# MPL115A1-Breakout-v12.net
KiCad netlist of a schematic drawn in EAGLE
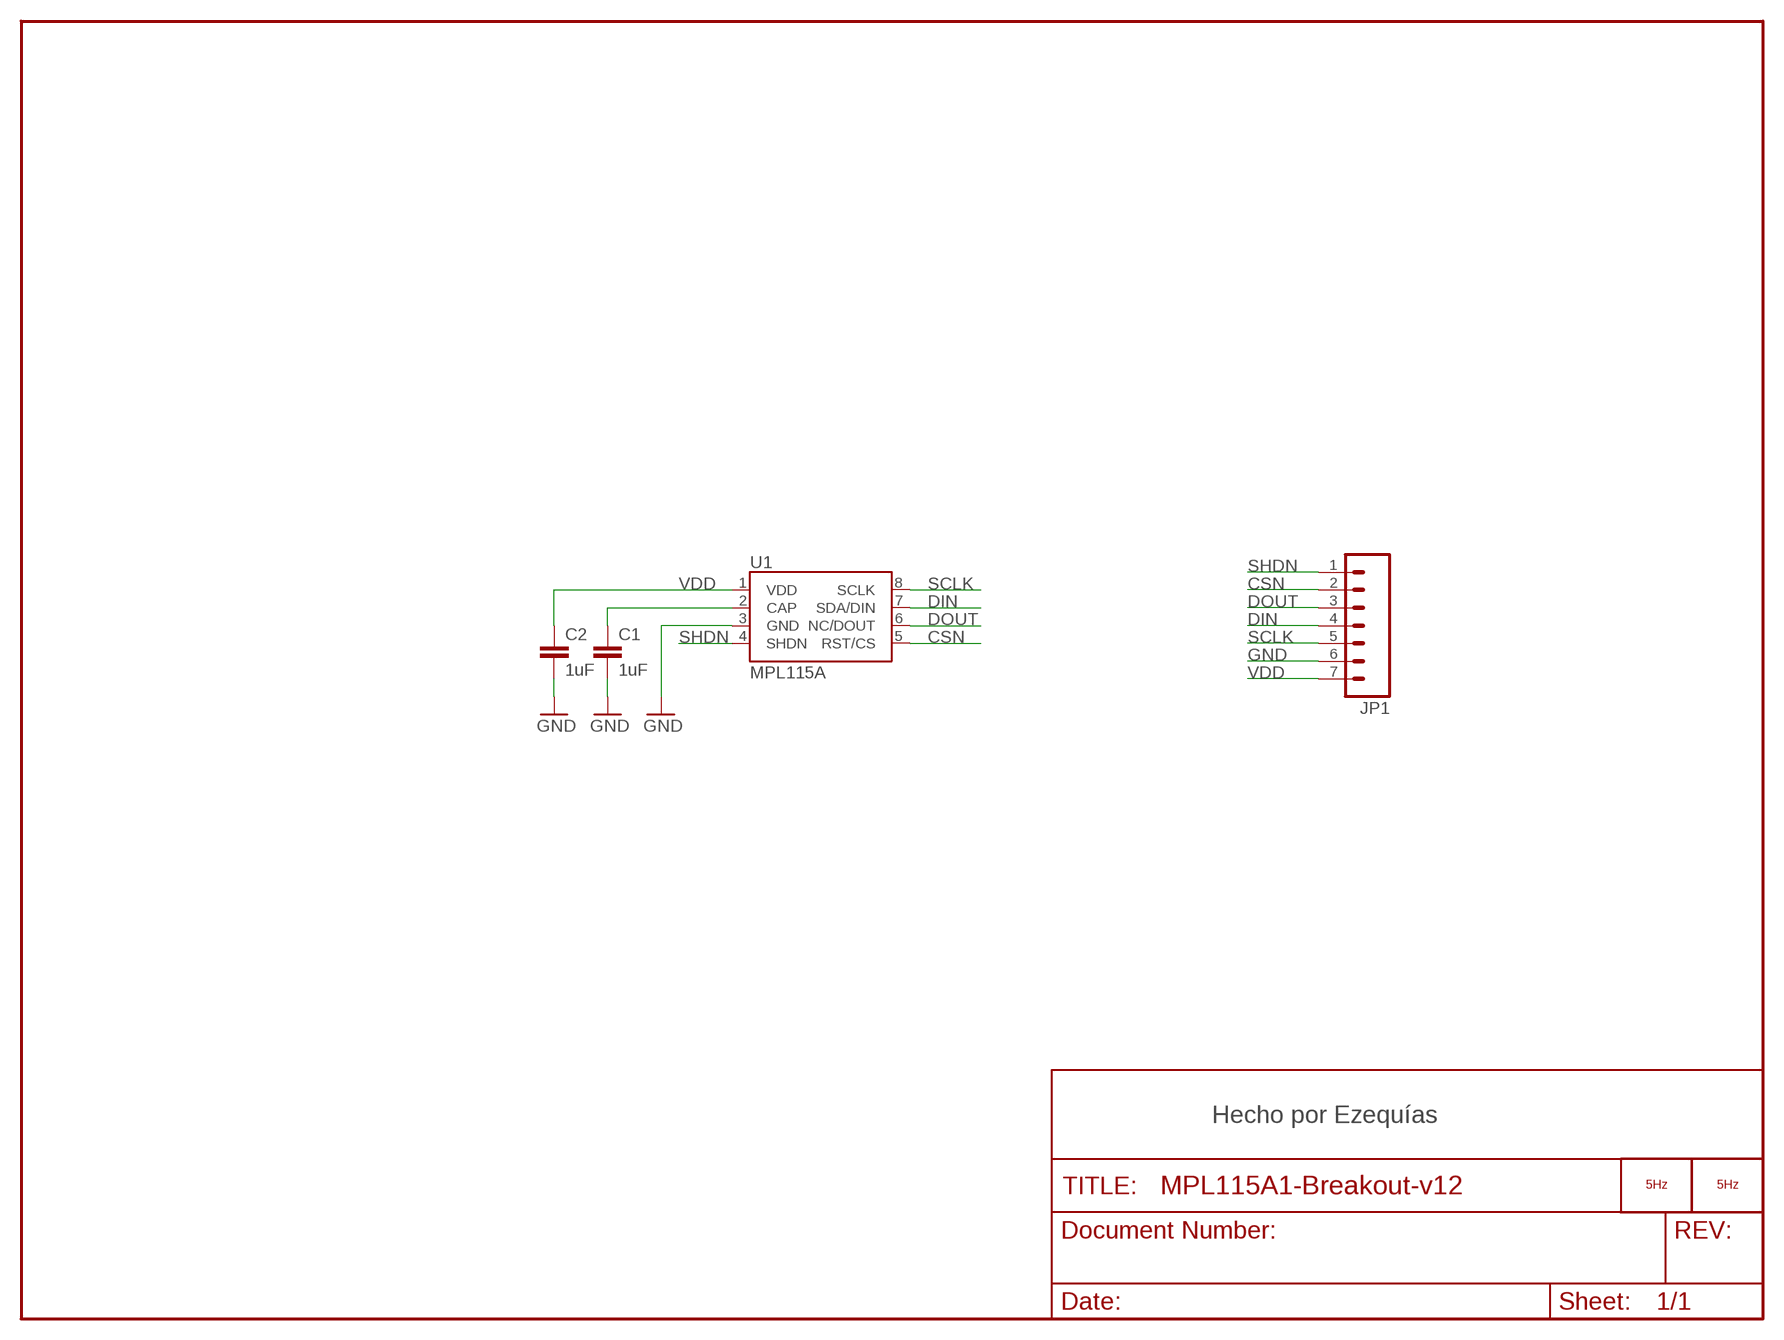
[diagram p0: schematic, sheet 1]

(export (version "E")
  (design (tool "Eeschema 10.0.6"))
  (components
    (comp (ref "C1")
      (value "1uF")
      (footprint "eagle-import:0603-CAP")
      (libsource (lib "eagle-import") (part "CAP0603-CAP"))
    )
    (comp (ref "C2")
      (value "1uF")
      (footprint "eagle-import:0603-CAP")
      (libsource (lib "eagle-import") (part "CAP0603-CAP"))
    )
    (comp (ref "JP1")
      (value "M07")
      (footprint "eagle-import:1X07")
      (libsource (lib "eagle-import") (part "M07"))
    )
    (comp (ref "LOGO1")
      (value "LOGO_5HZ_H_COOPER_10MM")
      (footprint "eagle-import:5HZ_LOGO_H_COOPER_10MM")
      (libsource (lib "eagle-import") (part "LOGO_5HZ_H_COOPER_10MM"))
    )
    (comp (ref "LOGO2")
      (value "LOGO_5HZ_H_5MM")
      (footprint "eagle-import:5HZ_LOGO_H_5MM")
      (libsource (lib "eagle-import") (part "LOGO_5HZ_H_5MM"))
    )
    (comp (ref "U1")
      (value "MPL115A")
      (footprint "eagle-import:LGA8")
      (libsource (lib "eagle-import") (part "MPL115A"))
    )
  )
  (nets
    (net (code "1") (name "/CSN") (class "Default")
      (node (ref "JP1") (pin "2") (pinfunction "2_2") (pintype "passive"))
      (node (ref "U1") (pin "5") (pinfunction "RST/CS_5") (pintype "bidirectional"))
    )
    (net (code "2") (name "/DIN") (class "Default")
      (node (ref "JP1") (pin "4") (pinfunction "4_4") (pintype "passive"))
      (node (ref "U1") (pin "7") (pinfunction "SDA/DIN_7") (pintype "bidirectional"))
    )
    (net (code "3") (name "/DOUT") (class "Default")
      (node (ref "JP1") (pin "3") (pinfunction "3_3") (pintype "passive"))
      (node (ref "U1") (pin "6") (pinfunction "NC/DOUT_6") (pintype "bidirectional"))
    )
    (net (code "4") (name "/SCLK") (class "Default")
      (node (ref "JP1") (pin "5") (pinfunction "5_5") (pintype "passive"))
      (node (ref "U1") (pin "8") (pinfunction "SCLK_8") (pintype "bidirectional"))
    )
    (net (code "5") (name "/SHDN") (class "Default")
      (node (ref "JP1") (pin "1") (pinfunction "1_1") (pintype "passive"))
      (node (ref "U1") (pin "4") (pinfunction "SHDN_4") (pintype "bidirectional"))
    )
    (net (code "6") (name "/VDD") (class "Default")
      (node (ref "C2") (pin "1") (pinfunction "1_1") (pintype "passive"))
      (node (ref "JP1") (pin "7") (pinfunction "7_7") (pintype "passive"))
      (node (ref "U1") (pin "1") (pinfunction "VDD_1") (pintype "bidirectional"))
    )
    (net (code "7") (name "GND") (class "Default")
      (node (ref "C1") (pin "2") (pinfunction "2_2") (pintype "passive"))
      (node (ref "C2") (pin "2") (pinfunction "2_2") (pintype "passive"))
      (node (ref "JP1") (pin "6") (pinfunction "6_6") (pintype "passive"))
      (node (ref "U1") (pin "3") (pinfunction "GND_3") (pintype "bidirectional"))
    )
    (net (code "8") (name "Net-(U1-CAP)") (class "Default")
      (node (ref "C1") (pin "1") (pinfunction "1_1") (pintype "passive"))
      (node (ref "U1") (pin "2") (pinfunction "CAP_2") (pintype "bidirectional"))
    )
  )
)
